# differential_lowpass.net
KiCad netlist of a schematic drawn in Altium Designer
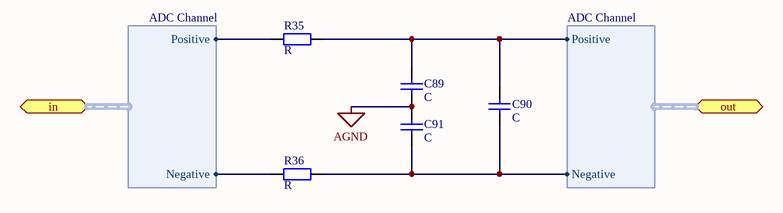
[diagram p0: differential_lowpass.SchDoc]

(export (version "E")
  (design (tool "Eeschema 10.0.6"))
  (components
    (comp (ref "C89")
      (value "C")
      (footprint "C0603")
      (description "Generic capacitor")
      (libsource (lib "GG") (part "Cap"))
    )
    (comp (ref "C90")
      (value "C")
      (footprint "C0603")
      (description "Generic capacitor")
      (libsource (lib "GG") (part "Cap"))
    )
    (comp (ref "C91")
      (value "C")
      (footprint "C0603")
      (description "Generic capacitor")
      (libsource (lib "GG") (part "Cap"))
    )
    (comp (ref "R35")
      (value "R")
      (footprint "0603")
      (description "Generic resistor")
      (libsource (lib "GG") (part "Res"))
    )
    (comp (ref "R36")
      (value "R")
      (footprint "0603")
      (description "Generic resistor")
      (libsource (lib "GG") (part "Res"))
    )
  )
  (nets
    (net (code "4") (name "AGND") (class "Default")
      (node (ref "C89") (pin "2") (pinfunction "2_2") (pintype "passive"))
      (node (ref "C91") (pin "1") (pinfunction "1_1") (pintype "passive"))
    )
    (net (code "5") (name "Net-(C89-Pad1)") (class "Default")
      (node (ref "C89") (pin "1") (pinfunction "1_1") (pintype "passive"))
      (node (ref "C90") (pin "1") (pinfunction "1_1") (pintype "passive"))
      (node (ref "R35") (pin "2") (pinfunction "2_2") (pintype "passive"))
    )
    (net (code "6") (name "Net-(C90-Pad2)") (class "Default")
      (node (ref "C90") (pin "2") (pinfunction "2_2") (pintype "passive"))
      (node (ref "C91") (pin "2") (pinfunction "2_2") (pintype "passive"))
      (node (ref "R36") (pin "2") (pinfunction "2_2") (pintype "passive"))
    )
    (net (code "7") (name "unconnected-(R35-Pad1)") (class "Default")
      (node (ref "R35") (pin "1") (pinfunction "1_1") (pintype "passive"))
    )
    (net (code "8") (name "unconnected-(R36-Pad1)") (class "Default")
      (node (ref "R36") (pin "1") (pinfunction "1_1") (pintype "passive"))
    )
  )
)
